# VisualightMicroBulb_041.net
KiCad netlist of a schematic drawn in EAGLE
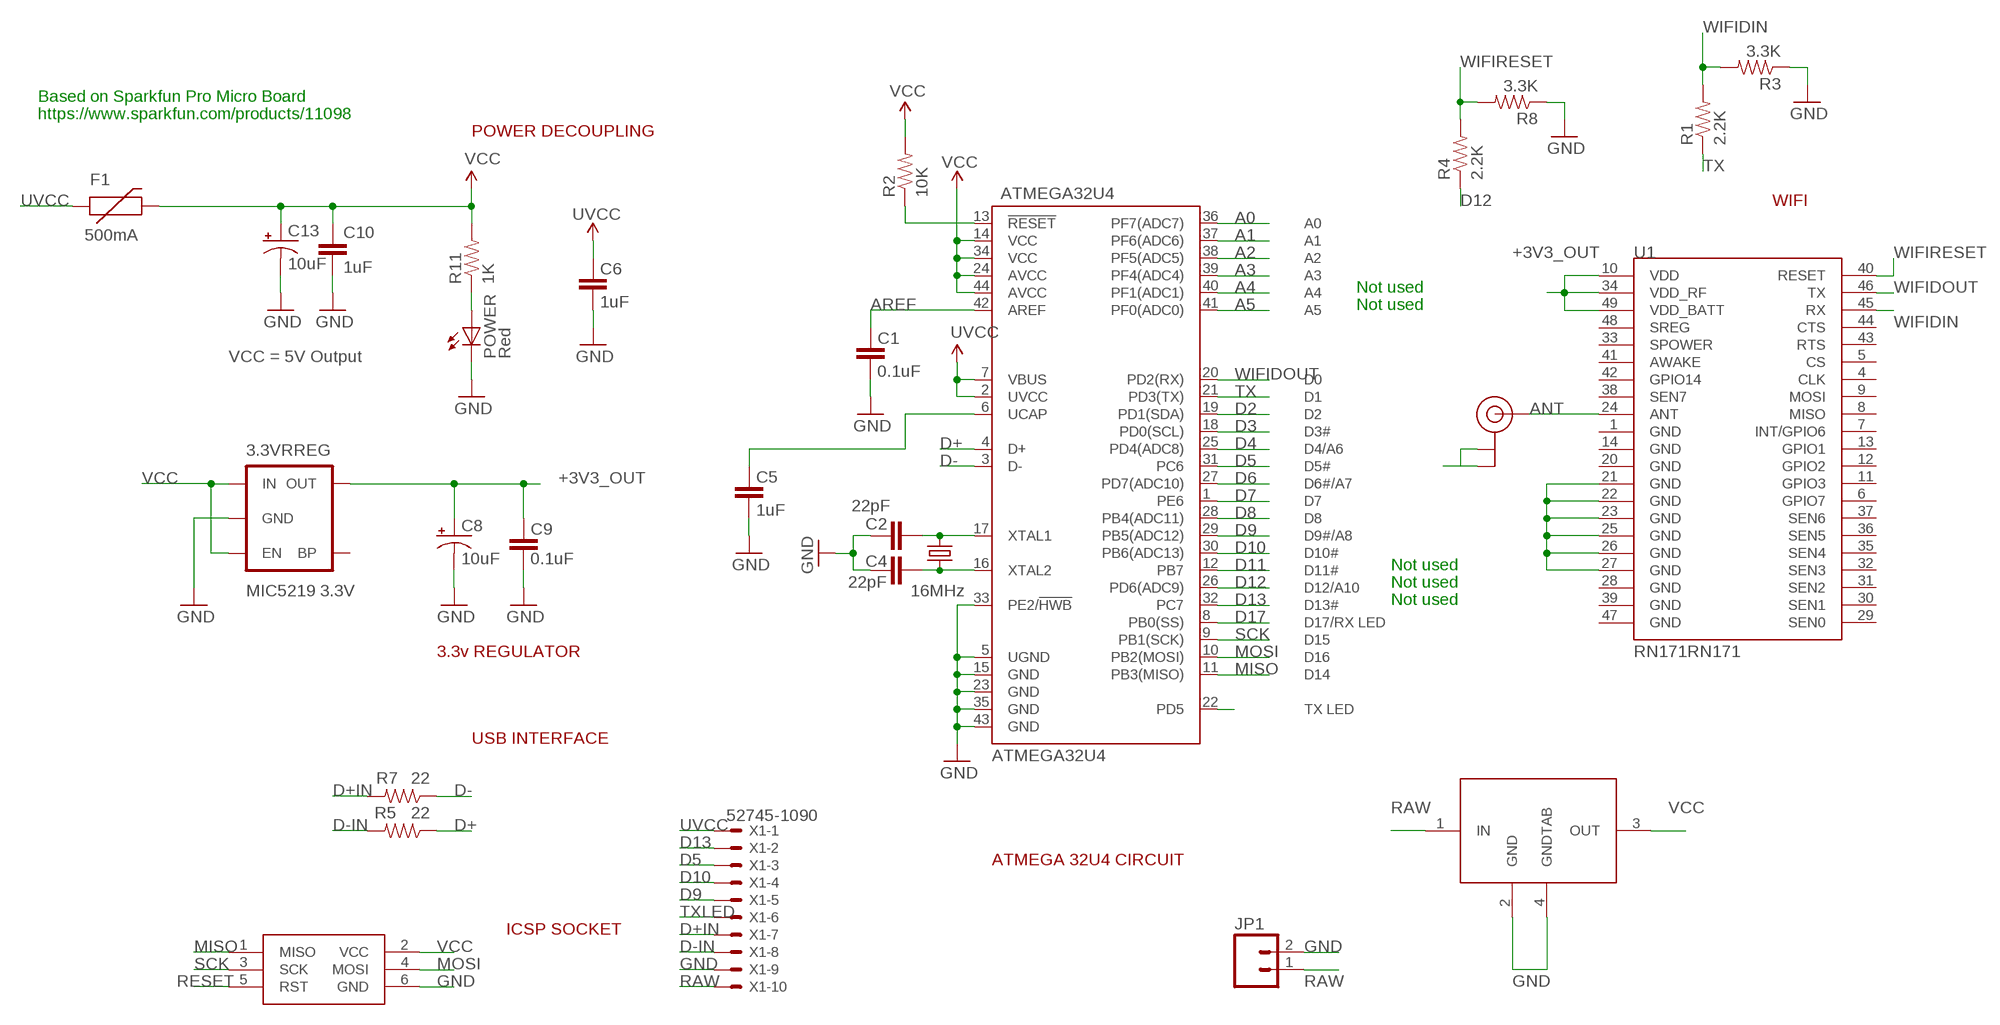
[diagram p0: schematic, sheet 1]

(export (version "E")
  (design (tool "Eeschema 10.0.6"))
  (components
    (comp (ref "3.3VRREG")
      (value "MIC5219 3.3V")
      (footprint "eagle-import:SOT23-5")
      (libsource (lib "eagle-import") (part "V_REG_MIC52193.3V"))
    )
    (comp (ref "ATMEGA32U4")
      (value "ATMEGA32U4")
      (footprint "eagle-import:SPARKFUN-DIGITALIC_TQFP44")
      (libsource (lib "eagle-import") (part "ATMEGA32U4TQFP"))
    )
    (comp (ref "C1")
      (value "0.1uF")
      (footprint "eagle-import:0402-CAP")
      (libsource (lib "eagle-import") (part "CAP0402-CAP"))
    )
    (comp (ref "C2")
      (value "22pF")
      (footprint "eagle-import:0402-CAP")
      (libsource (lib "eagle-import") (part "CAP0402-CAP"))
    )
    (comp (ref "C4")
      (value "22pF")
      (footprint "eagle-import:0402-CAP")
      (libsource (lib "eagle-import") (part "CAP0402-CAP"))
    )
    (comp (ref "C5")
      (value "1uF")
      (footprint "eagle-import:0402-CAP")
      (libsource (lib "eagle-import") (part "CAP0402-CAP"))
    )
    (comp (ref "C6")
      (value "1uF")
      (footprint "eagle-import:0402-CAP")
      (libsource (lib "eagle-import") (part "CAP0402-CAP"))
    )
    (comp (ref "C8")
      (value "10uF")
      (footprint "eagle-import:EIA3216")
      (libsource (lib "eagle-import") (part "CAP_POL1206"))
    )
    (comp (ref "C9")
      (value "0.1uF")
      (footprint "eagle-import:0402-CAP")
      (libsource (lib "eagle-import") (part "CAP0402-CAP"))
    )
    (comp (ref "C10")
      (value "1uF")
      (footprint "eagle-import:0402-CAP")
      (libsource (lib "eagle-import") (part "CAP0402-CAP"))
    )
    (comp (ref "C13")
      (value "10uF")
      (footprint "eagle-import:EIA3216")
      (libsource (lib "eagle-import") (part "CAP_POL1206"))
    )
    (comp (ref "F1")
      (value "500mA")
      (footprint "eagle-import:PTC-1206")
      (libsource (lib "eagle-import") (part "PTCSMD"))
    )
    (comp (ref "ISP1")
      (value "AVRISP-6")
      (footprint "eagle-import:AVRISP")
      (libsource (lib "eagle-import") (part "AVRISP-6"))
    )
    (comp (ref "JP1")
      (value "M02PTH")
      (footprint "eagle-import:1X02")
      (libsource (lib "eagle-import") (part "M02PTH"))
    )
    (comp (ref "POWER")
      (value "Red")
      (footprint "eagle-import:LED-0603")
      (libsource (lib "eagle-import") (part "LED0603"))
    )
    (comp (ref "R1")
      (value "2.2K")
      (footprint "eagle-import:0402-RES")
      (libsource (lib "eagle-import") (part "RESISTOR0402-RES"))
    )
    (comp (ref "R2")
      (value "10K")
      (footprint "eagle-import:0402-RES")
      (libsource (lib "eagle-import") (part "RESISTOR0402-RES"))
    )
    (comp (ref "R3")
      (value "3.3K")
      (footprint "eagle-import:0402-RES")
      (libsource (lib "eagle-import") (part "RESISTOR0402-RES"))
    )
    (comp (ref "R4")
      (value "2.2K")
      (footprint "eagle-import:0402-RES")
      (libsource (lib "eagle-import") (part "RESISTOR0402-RES"))
    )
    (comp (ref "R5")
      (value "22")
      (footprint "eagle-import:0402-RES")
      (libsource (lib "eagle-import") (part "RESISTOR0402-RES"))
    )
    (comp (ref "R7")
      (value "22")
      (footprint "eagle-import:0402-RES")
      (libsource (lib "eagle-import") (part "RESISTOR0402-RES"))
    )
    (comp (ref "R8")
      (value "3.3K")
      (footprint "eagle-import:0402-RES")
      (libsource (lib "eagle-import") (part "RESISTOR0402-RES"))
    )
    (comp (ref "R11")
      (value "1K")
      (footprint "eagle-import:0402-RES")
      (libsource (lib "eagle-import") (part "RESISTOR0402-RES"))
    )
    (comp (ref "U$1")
      (value "U.FL")
      (footprint "eagle-import:U.FL")
      (libsource (lib "eagle-import") (part "U.FL"))
    )
    (comp (ref "U$2")
      (value "MIC5239")
      (footprint "eagle-import:SOT223")
      (libsource (lib "eagle-import") (part "MIC5239"))
    )
    (comp (ref "U1")
      (value "RN171RN171")
      (footprint "eagle-import:RN171")
      (libsource (lib "eagle-import") (part "RN171RN171"))
    )
    (comp (ref "X1")
      (value "52745-1090")
      (footprint "eagle-import:52745-1090")
      (libsource (lib "eagle-import") (part "52745-1090"))
    )
    (comp (ref "Y1")
      (value "16MHz")
      (footprint "eagle-import:CRYSTAL-SMD-5X3")
      (libsource (lib "eagle-import") (part "CRYSTAL5X3"))
    )
  )
  (nets
    (net (code "1") (name "/+3V3_OUT") (class "Default")
      (node (ref "3.3VRREG") (pin "5") (pinfunction "OUT_5") (pintype "passive"))
      (node (ref "C8") (pin "A") (pinfunction "+_A") (pintype "passive"))
      (node (ref "C9") (pin "2") (pinfunction "2_2") (pintype "passive"))
      (node (ref "U1") (pin "10") (pinfunction "VDD_10") (pintype "bidirectional"))
      (node (ref "U1") (pin "34") (pinfunction "VDD_RF_34") (pintype "bidirectional"))
      (node (ref "U1") (pin "49") (pinfunction "VDD_BATT_49") (pintype "bidirectional"))
    )
    (net (code "2") (name "/A0") (class "Default")
      (node (ref "ATMEGA32U4") (pin "36") (pinfunction "PF7(ADC7)_36") (pintype "bidirectional"))
    )
    (net (code "3") (name "/A1") (class "Default")
      (node (ref "ATMEGA32U4") (pin "37") (pinfunction "PF6(ADC6)_37") (pintype "bidirectional"))
    )
    (net (code "4") (name "/A2") (class "Default")
      (node (ref "ATMEGA32U4") (pin "38") (pinfunction "PF5(ADC5)_38") (pintype "bidirectional"))
    )
    (net (code "5") (name "/A3") (class "Default")
      (node (ref "ATMEGA32U4") (pin "39") (pinfunction "PF4(ADC4)_39") (pintype "bidirectional"))
    )
    (net (code "6") (name "/A4") (class "Default")
      (node (ref "ATMEGA32U4") (pin "40") (pinfunction "PF1(ADC1)_40") (pintype "bidirectional"))
    )
    (net (code "7") (name "/A5") (class "Default")
      (node (ref "ATMEGA32U4") (pin "41") (pinfunction "PF0(ADC0)_41") (pintype "bidirectional"))
    )
    (net (code "8") (name "/ANT") (class "Default")
      (node (ref "U$1") (pin "P$3") (pinfunction "SIGNAL_P$3") (pintype "bidirectional"))
      (node (ref "U1") (pin "24") (pinfunction "ANT_24") (pintype "bidirectional"))
    )
    (net (code "9") (name "/AREF") (class "Default")
      (node (ref "ATMEGA32U4") (pin "42") (pinfunction "AREF_42") (pintype "bidirectional"))
      (node (ref "C1") (pin "2") (pinfunction "2_2") (pintype "passive"))
    )
    (net (code "10") (name "/D+") (class "Default")
      (node (ref "ATMEGA32U4") (pin "4") (pinfunction "D+_4") (pintype "bidirectional"))
      (node (ref "R5") (pin "1") (pinfunction "1_1") (pintype "passive"))
    )
    (net (code "11") (name "/D+IN") (class "Default")
      (node (ref "R7") (pin "2") (pinfunction "2_2") (pintype "passive"))
      (node (ref "X1") (pin "7") (pinfunction "S_7") (pintype "passive"))
    )
    (net (code "12") (name "/D-") (class "Default")
      (node (ref "ATMEGA32U4") (pin "3") (pinfunction "D-_3") (pintype "bidirectional"))
      (node (ref "R7") (pin "1") (pinfunction "1_1") (pintype "passive"))
    )
    (net (code "13") (name "/D-IN") (class "Default")
      (node (ref "R5") (pin "2") (pinfunction "2_2") (pintype "passive"))
      (node (ref "X1") (pin "8") (pinfunction "S_8") (pintype "passive"))
    )
    (net (code "14") (name "/D2") (class "Default")
      (node (ref "ATMEGA32U4") (pin "19") (pinfunction "PD1(SDA)_19") (pintype "bidirectional"))
    )
    (net (code "15") (name "/D3") (class "Default")
      (node (ref "ATMEGA32U4") (pin "18") (pinfunction "PD0(SCL)_18") (pintype "bidirectional"))
    )
    (net (code "16") (name "/D4") (class "Default")
      (node (ref "ATMEGA32U4") (pin "25") (pinfunction "PD4(ADC8)_25") (pintype "bidirectional"))
    )
    (net (code "17") (name "/D5") (class "Default")
      (node (ref "ATMEGA32U4") (pin "31") (pinfunction "PC6_31") (pintype "bidirectional"))
      (node (ref "X1") (pin "3") (pinfunction "S_3") (pintype "passive"))
    )
    (net (code "18") (name "/D6") (class "Default")
      (node (ref "ATMEGA32U4") (pin "27") (pinfunction "PD7(ADC10)_27") (pintype "bidirectional"))
    )
    (net (code "19") (name "/D7") (class "Default")
      (node (ref "ATMEGA32U4") (pin "1") (pinfunction "PE6_1") (pintype "bidirectional"))
    )
    (net (code "20") (name "/D8") (class "Default")
      (node (ref "ATMEGA32U4") (pin "28") (pinfunction "PB4(ADC11)_28") (pintype "bidirectional"))
    )
    (net (code "21") (name "/D9") (class "Default")
      (node (ref "ATMEGA32U4") (pin "29") (pinfunction "PB5(ADC12)_29") (pintype "bidirectional"))
      (node (ref "X1") (pin "5") (pinfunction "S_5") (pintype "passive"))
    )
    (net (code "22") (name "/D10") (class "Default")
      (node (ref "ATMEGA32U4") (pin "30") (pinfunction "PB6(ADC13)_30") (pintype "bidirectional"))
      (node (ref "X1") (pin "4") (pinfunction "S_4") (pintype "passive"))
    )
    (net (code "23") (name "/D11") (class "Default")
      (node (ref "ATMEGA32U4") (pin "12") (pinfunction "PB7_12") (pintype "bidirectional"))
    )
    (net (code "24") (name "/D12") (class "Default")
      (node (ref "ATMEGA32U4") (pin "26") (pinfunction "PD6(ADC9)_26") (pintype "bidirectional"))
      (node (ref "R4") (pin "1") (pinfunction "1_1") (pintype "passive"))
    )
    (net (code "25") (name "/D13") (class "Default")
      (node (ref "ATMEGA32U4") (pin "32") (pinfunction "PC7_32") (pintype "bidirectional"))
      (node (ref "X1") (pin "2") (pinfunction "S_2") (pintype "passive"))
    )
    (net (code "26") (name "/D17") (class "Default")
      (node (ref "ATMEGA32U4") (pin "8") (pinfunction "PB0(SS)_8") (pintype "bidirectional"))
    )
    (net (code "27") (name "/MISO") (class "Default")
      (node (ref "ATMEGA32U4") (pin "11") (pinfunction "PB3(MISO)_11") (pintype "bidirectional"))
      (node (ref "ISP1") (pin "1") (pinfunction "MISO_1") (pintype "input"))
    )
    (net (code "28") (name "/MOSI") (class "Default")
      (node (ref "ATMEGA32U4") (pin "10") (pinfunction "PB2(MOSI)_10") (pintype "bidirectional"))
      (node (ref "ISP1") (pin "4") (pinfunction "MOSI_4") (pintype "output"))
    )
    (net (code "29") (name "/RAW") (class "Default")
      (node (ref "JP1") (pin "1") (pinfunction "1_1") (pintype "passive"))
      (node (ref "U$2") (pin "1") (pinfunction "IN_1") (pintype "input"))
      (node (ref "X1") (pin "10") (pinfunction "S_10") (pintype "passive"))
    )
    (net (code "30") (name "/RESET") (class "Default")
      (node (ref "ATMEGA32U4") (pin "13") (pinfunction "~{RESET}_13") (pintype "bidirectional"))
      (node (ref "ISP1") (pin "5") (pinfunction "RST_5") (pintype "output"))
      (node (ref "R2") (pin "1") (pinfunction "1_1") (pintype "passive"))
    )
    (net (code "31") (name "/SCK") (class "Default")
      (node (ref "ATMEGA32U4") (pin "9") (pinfunction "PB1(SCK)_9") (pintype "bidirectional"))
      (node (ref "ISP1") (pin "3") (pinfunction "SCK_3") (pintype "output"))
    )
    (net (code "32") (name "/TX") (class "Default")
      (node (ref "ATMEGA32U4") (pin "21") (pinfunction "PD3(TX)_21") (pintype "bidirectional"))
      (node (ref "R1") (pin "1") (pinfunction "1_1") (pintype "passive"))
    )
    (net (code "33") (name "/TXLED") (class "Default")
      (node (ref "ATMEGA32U4") (pin "22") (pinfunction "PD5_22") (pintype "bidirectional"))
      (node (ref "X1") (pin "6") (pinfunction "S_6") (pintype "passive"))
    )
    (net (code "34") (name "/WIFIDIN") (class "Default")
      (node (ref "R1") (pin "2") (pinfunction "2_2") (pintype "passive"))
      (node (ref "R3") (pin "2") (pinfunction "2_2") (pintype "passive"))
      (node (ref "U1") (pin "45") (pinfunction "RX_45") (pintype "bidirectional"))
    )
    (net (code "35") (name "/WIFIDOUT") (class "Default")
      (node (ref "ATMEGA32U4") (pin "20") (pinfunction "PD2(RX)_20") (pintype "bidirectional"))
      (node (ref "U1") (pin "46") (pinfunction "TX_46") (pintype "bidirectional"))
    )
    (net (code "36") (name "/WIFIRESET") (class "Default")
      (node (ref "R4") (pin "2") (pinfunction "2_2") (pintype "passive"))
      (node (ref "R8") (pin "2") (pinfunction "2_2") (pintype "passive"))
      (node (ref "U1") (pin "40") (pinfunction "RESET_40") (pintype "bidirectional"))
    )
    (net (code "37") (name "GND") (class "Default")
      (node (ref "3.3VRREG") (pin "2") (pinfunction "GND_2") (pintype "input"))
      (node (ref "ATMEGA32U4") (pin "15") (pinfunction "GND_15") (pintype "bidirectional"))
      (node (ref "ATMEGA32U4") (pin "23") (pinfunction "GND_23") (pintype "bidirectional"))
      (node (ref "ATMEGA32U4") (pin "33") (pinfunction "PE2/~{HWB}_33") (pintype "bidirectional"))
      (node (ref "ATMEGA32U4") (pin "35") (pinfunction "GND_35") (pintype "bidirectional"))
      (node (ref "ATMEGA32U4") (pin "43") (pinfunction "GND_43") (pintype "bidirectional"))
      (node (ref "ATMEGA32U4") (pin "5") (pinfunction "UGND_5") (pintype "bidirectional"))
      (node (ref "C1") (pin "1") (pinfunction "1_1") (pintype "passive"))
      (node (ref "C10") (pin "2") (pinfunction "2_2") (pintype "passive"))
      (node (ref "C13") (pin "C") (pinfunction "-_C") (pintype "passive"))
      (node (ref "C2") (pin "2") (pinfunction "2_2") (pintype "passive"))
      (node (ref "C4") (pin "2") (pinfunction "2_2") (pintype "passive"))
      (node (ref "C5") (pin "1") (pinfunction "1_1") (pintype "passive"))
      (node (ref "C6") (pin "1") (pinfunction "1_1") (pintype "passive"))
      (node (ref "C8") (pin "C") (pinfunction "-_C") (pintype "passive"))
      (node (ref "C9") (pin "1") (pinfunction "1_1") (pintype "passive"))
      (node (ref "ISP1") (pin "6") (pinfunction "GND_6") (pintype "power_in"))
      (node (ref "JP1") (pin "2") (pinfunction "2_2") (pintype "passive"))
      (node (ref "POWER") (pin "C") (pinfunction "C_C") (pintype "passive"))
      (node (ref "R3") (pin "1") (pinfunction "1_1") (pintype "passive"))
      (node (ref "R8") (pin "1") (pinfunction "1_1") (pintype "passive"))
      (node (ref "U$1") (pin "P$1") (pinfunction "GND_P$1") (pintype "bidirectional"))
      (node (ref "U$1") (pin "P$2") (pinfunction "GND_P$2") (pintype "bidirectional"))
      (node (ref "U$2") (pin "2") (pinfunction "GND_2") (pintype "power_in"))
      (node (ref "U$2") (pin "4") (pinfunction "GNDTAB_4") (pintype "power_in"))
      (node (ref "U1") (pin "21") (pinfunction "GND_21") (pintype "bidirectional"))
      (node (ref "U1") (pin "22") (pinfunction "GND_22") (pintype "bidirectional"))
      (node (ref "U1") (pin "23") (pinfunction "GND_23") (pintype "bidirectional"))
      (node (ref "U1") (pin "25") (pinfunction "GND_25") (pintype "bidirectional"))
      (node (ref "U1") (pin "26") (pinfunction "GND_26") (pintype "bidirectional"))
      (node (ref "U1") (pin "27") (pinfunction "GND_27") (pintype "bidirectional"))
      (node (ref "X1") (pin "9") (pinfunction "S_9") (pintype "passive"))
    )
    (net (code "38") (name "Net-(ATMEGA32U4-UCAP)") (class "Default")
      (node (ref "ATMEGA32U4") (pin "6") (pinfunction "UCAP_6") (pintype "bidirectional"))
      (node (ref "C5") (pin "2") (pinfunction "2_2") (pintype "passive"))
    )
    (net (code "39") (name "Net-(ATMEGA32U4-XTAL1)") (class "Default")
      (node (ref "ATMEGA32U4") (pin "17") (pinfunction "XTAL1_17") (pintype "bidirectional"))
      (node (ref "C2") (pin "1") (pinfunction "1_1") (pintype "passive"))
      (node (ref "Y1") (pin "3") (pinfunction "2_3") (pintype "passive"))
    )
    (net (code "40") (name "Net-(ATMEGA32U4-XTAL2)") (class "Default")
      (node (ref "ATMEGA32U4") (pin "16") (pinfunction "XTAL2_16") (pintype "bidirectional"))
      (node (ref "C4") (pin "1") (pinfunction "1_1") (pintype "passive"))
      (node (ref "Y1") (pin "1") (pinfunction "1_1") (pintype "passive"))
    )
    (net (code "41") (name "Net-(POWER-PadA)") (class "Default")
      (node (ref "POWER") (pin "A") (pinfunction "A_A") (pintype "passive"))
      (node (ref "R11") (pin "1") (pinfunction "1_1") (pintype "passive"))
    )
    (net (code "42") (name "UVCC") (class "Default")
      (node (ref "ATMEGA32U4") (pin "2") (pinfunction "UVCC_2") (pintype "bidirectional"))
      (node (ref "ATMEGA32U4") (pin "7") (pinfunction "VBUS_7") (pintype "bidirectional"))
      (node (ref "C6") (pin "2") (pinfunction "2_2") (pintype "passive"))
      (node (ref "F1") (pin "1") (pinfunction "1_1") (pintype "bidirectional"))
      (node (ref "X1") (pin "1") (pinfunction "S_1") (pintype "passive"))
    )
    (net (code "43") (name "VCC") (class "Default")
      (node (ref "3.3VRREG") (pin "1") (pinfunction "IN_1") (pintype "input"))
      (node (ref "3.3VRREG") (pin "3") (pinfunction "EN_3") (pintype "input"))
      (node (ref "ATMEGA32U4") (pin "14") (pinfunction "VCC_14") (pintype "bidirectional"))
      (node (ref "ATMEGA32U4") (pin "24") (pinfunction "AVCC_24") (pintype "bidirectional"))
      (node (ref "ATMEGA32U4") (pin "34") (pinfunction "VCC_34") (pintype "bidirectional"))
      (node (ref "ATMEGA32U4") (pin "44") (pinfunction "AVCC_44") (pintype "bidirectional"))
      (node (ref "C10") (pin "1") (pinfunction "1_1") (pintype "passive"))
      (node (ref "C13") (pin "A") (pinfunction "+_A") (pintype "passive"))
      (node (ref "F1") (pin "2") (pinfunction "2_2") (pintype "bidirectional"))
      (node (ref "ISP1") (pin "2") (pinfunction "VCC_2") (pintype "power_in"))
      (node (ref "R11") (pin "2") (pinfunction "2_2") (pintype "passive"))
      (node (ref "R2") (pin "2") (pinfunction "2_2") (pintype "passive"))
      (node (ref "U$2") (pin "3") (pinfunction "OUT_3") (pintype "output"))
    )
    (net (code "44") (name "unconnected-(3.3VRREG-BP-Pad4)") (class "Default")
      (node (ref "3.3VRREG") (pin "4") (pinfunction "BP_4") (pintype "input"))
    )
    (net (code "45") (name "unconnected-(U1-AWAKE-Pad41)") (class "Default")
      (node (ref "U1") (pin "41") (pinfunction "AWAKE_41") (pintype "bidirectional"))
    )
    (net (code "46") (name "unconnected-(U1-CLK-Pad4)") (class "Default")
      (node (ref "U1") (pin "4") (pinfunction "CLK_4") (pintype "bidirectional"))
    )
    (net (code "47") (name "unconnected-(U1-CS-Pad5)") (class "Default")
      (node (ref "U1") (pin "5") (pinfunction "CS_5") (pintype "bidirectional"))
    )
    (net (code "48") (name "unconnected-(U1-CTS-Pad44)") (class "Default")
      (node (ref "U1") (pin "44") (pinfunction "CTS_44") (pintype "bidirectional"))
    )
    (net (code "49") (name "unconnected-(U1-GND-Pad1)") (class "Default")
      (node (ref "U1") (pin "1") (pinfunction "GND_1") (pintype "bidirectional"))
    )
    (net (code "50") (name "unconnected-(U1-GND-Pad14)") (class "Default")
      (node (ref "U1") (pin "14") (pinfunction "GND_14") (pintype "bidirectional"))
    )
    (net (code "51") (name "unconnected-(U1-GND-Pad20)") (class "Default")
      (node (ref "U1") (pin "20") (pinfunction "GND_20") (pintype "bidirectional"))
    )
    (net (code "52") (name "unconnected-(U1-GND-Pad28)") (class "Default")
      (node (ref "U1") (pin "28") (pinfunction "GND_28") (pintype "bidirectional"))
    )
    (net (code "53") (name "unconnected-(U1-GND-Pad39)") (class "Default")
      (node (ref "U1") (pin "39") (pinfunction "GND_39") (pintype "bidirectional"))
    )
    (net (code "54") (name "unconnected-(U1-GND-Pad47)") (class "Default")
      (node (ref "U1") (pin "47") (pinfunction "GND_47") (pintype "bidirectional"))
    )
    (net (code "55") (name "unconnected-(U1-GPIO1-Pad13)") (class "Default")
      (node (ref "U1") (pin "13") (pinfunction "GPIO1_13") (pintype "bidirectional"))
    )
    (net (code "56") (name "unconnected-(U1-GPIO2-Pad12)") (class "Default")
      (node (ref "U1") (pin "12") (pinfunction "GPIO2_12") (pintype "bidirectional"))
    )
    (net (code "57") (name "unconnected-(U1-GPIO3-Pad11)") (class "Default")
      (node (ref "U1") (pin "11") (pinfunction "GPIO3_11") (pintype "bidirectional"))
    )
    (net (code "58") (name "unconnected-(U1-GPIO7-Pad6)") (class "Default")
      (node (ref "U1") (pin "6") (pinfunction "GPIO7_6") (pintype "bidirectional"))
    )
    (net (code "59") (name "unconnected-(U1-GPIO14-Pad42)") (class "Default")
      (node (ref "U1") (pin "42") (pinfunction "GPIO14_42") (pintype "bidirectional"))
    )
    (net (code "60") (name "unconnected-(U1-INT{slash}GPIO6-Pad7)") (class "Default")
      (node (ref "U1") (pin "7") (pinfunction "INT/GPIO6_7") (pintype "bidirectional"))
    )
    (net (code "61") (name "unconnected-(U1-MISO-Pad8)") (class "Default")
      (node (ref "U1") (pin "8") (pinfunction "MISO_8") (pintype "bidirectional"))
    )
    (net (code "62") (name "unconnected-(U1-MOSI-Pad9)") (class "Default")
      (node (ref "U1") (pin "9") (pinfunction "MOSI_9") (pintype "bidirectional"))
    )
    (net (code "63") (name "unconnected-(U1-RTS-Pad43)") (class "Default")
      (node (ref "U1") (pin "43") (pinfunction "RTS_43") (pintype "bidirectional"))
    )
    (net (code "64") (name "unconnected-(U1-SEN0-Pad29)") (class "Default")
      (node (ref "U1") (pin "29") (pinfunction "SEN0_29") (pintype "bidirectional"))
    )
    (net (code "65") (name "unconnected-(U1-SEN1-Pad30)") (class "Default")
      (node (ref "U1") (pin "30") (pinfunction "SEN1_30") (pintype "bidirectional"))
    )
    (net (code "66") (name "unconnected-(U1-SEN2-Pad31)") (class "Default")
      (node (ref "U1") (pin "31") (pinfunction "SEN2_31") (pintype "bidirectional"))
    )
    (net (code "67") (name "unconnected-(U1-SEN3-Pad32)") (class "Default")
      (node (ref "U1") (pin "32") (pinfunction "SEN3_32") (pintype "bidirectional"))
    )
    (net (code "68") (name "unconnected-(U1-SEN4-Pad35)") (class "Default")
      (node (ref "U1") (pin "35") (pinfunction "SEN4_35") (pintype "bidirectional"))
    )
    (net (code "69") (name "unconnected-(U1-SEN5-Pad36)") (class "Default")
      (node (ref "U1") (pin "36") (pinfunction "SEN5_36") (pintype "bidirectional"))
    )
    (net (code "70") (name "unconnected-(U1-SEN6-Pad37)") (class "Default")
      (node (ref "U1") (pin "37") (pinfunction "SEN6_37") (pintype "bidirectional"))
    )
    (net (code "71") (name "unconnected-(U1-SEN7-Pad38)") (class "Default")
      (node (ref "U1") (pin "38") (pinfunction "SEN7_38") (pintype "bidirectional"))
    )
    (net (code "72") (name "unconnected-(U1-SPOWER-Pad33)") (class "Default")
      (node (ref "U1") (pin "33") (pinfunction "SPOWER_33") (pintype "bidirectional"))
    )
    (net (code "73") (name "unconnected-(U1-SREG-Pad48)") (class "Default")
      (node (ref "U1") (pin "48") (pinfunction "SREG_48") (pintype "bidirectional"))
    )
  )
)
